# Sheet1.net
KiCad netlist of a schematic drawn in Altium Designer
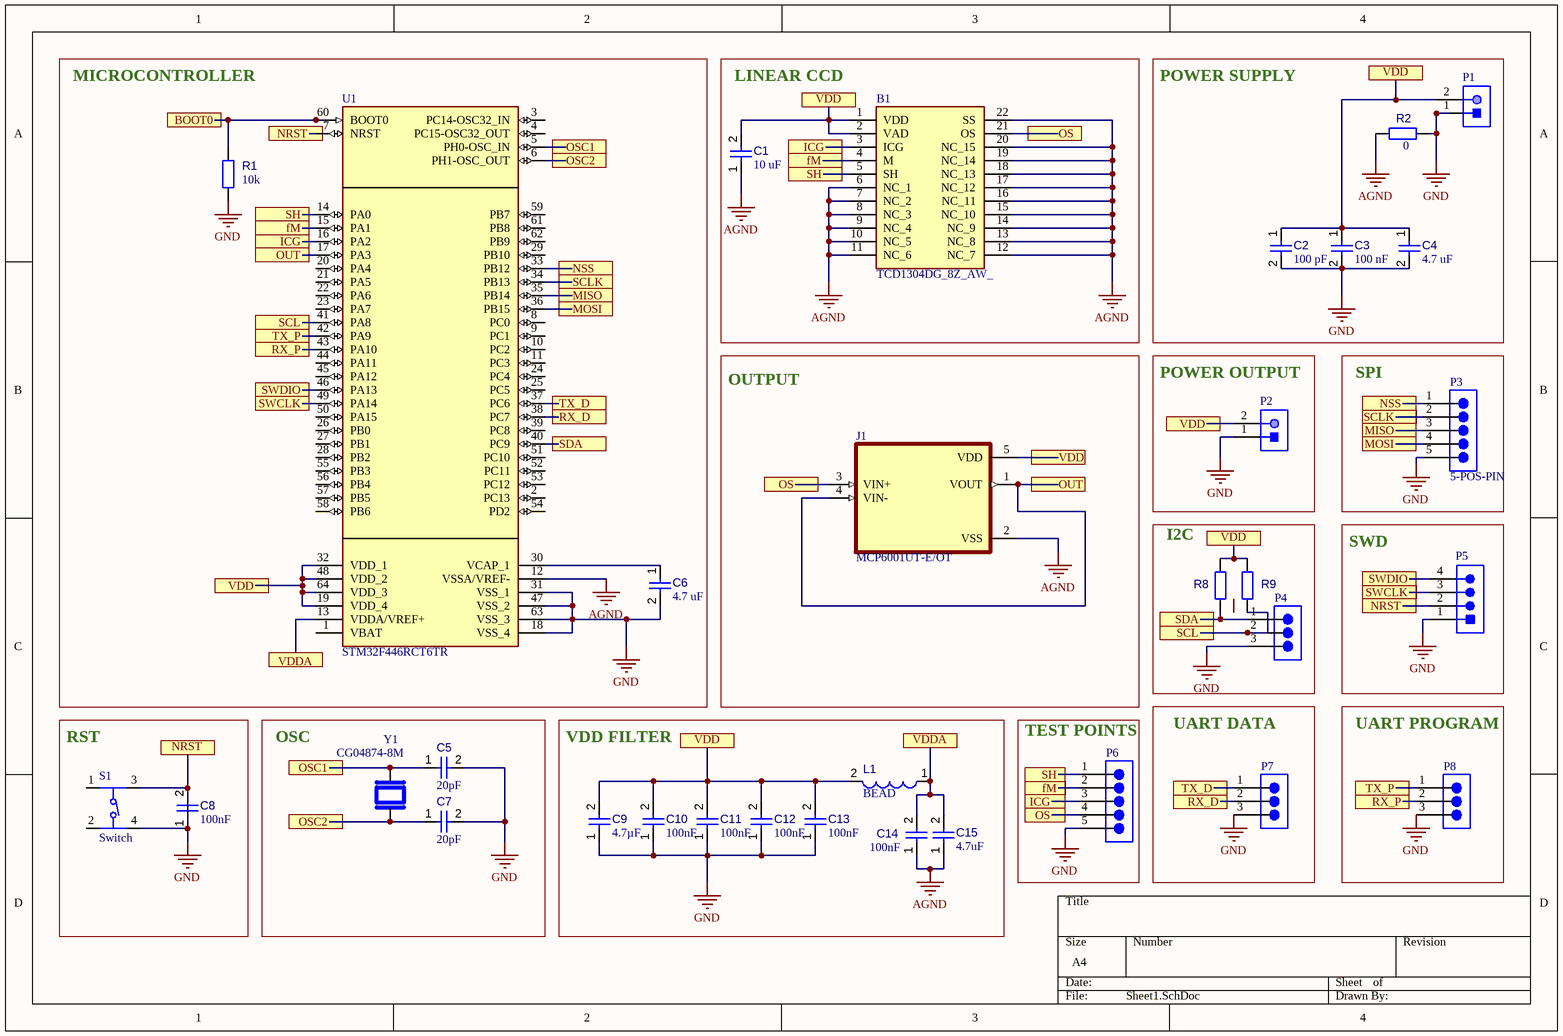
[diagram p0: Sheet1.SchDoc]

(export (version "E")
  (design (tool "Eeschema 10.0.6"))
  (components
    (comp (ref "B1")
      (value "TCD1304DG_8Z_AW_")
      (footprint "DIP1016W62P254L4160H372Q22N")
      (description "Image Sensors & Color Sensors CCD Linear Sensor 3648 8x20 54mm")
      (fields
        (field (name "MOUSER PART NUMBER") "757-TCD1304DG8ZAW")
        (field (name "MANUFACTURER_PART_NUMBER") "TCD1304DG(8Z,AW)")
      )
      (libsource (lib "Sensors") (part "TCD1304DG_8Z_AW_"))
    )
    (comp (ref "C1")
      (value "10 uF")
      (footprint "CAPC1005X56X25LL10T15")
      (description "Chip Capacitor, 0.1 uF, +/- 5%, 16 V, 0402 (1005 Metric)")
      (fields (field (name "TOLERANCE") "5%") (field (name "Comment") "Capacitor 0.1 uF +/- 5% 16 V 0402"))
      (libsource (lib "Francisco Spaltro") (part "CAP-NP-2"))
    )
    (comp (ref "C2")
      (value "100 pF")
      (footprint "CAPC2013X95X50LL10T25")
      (description "Chip Capacitor, 100 nF, +/- 10%, 50 V, 0805 (2012 Metric)")
      (fields (field (name "TOLERANCE") "10%") (field (name "Comment") "Capacitor 100 nF +/-10% 50 V 0805"))
      (libsource (lib "Francisco Spaltro") (part "CAP-NP-2"))
    )
    (comp (ref "C3")
      (value "100 nF")
      (footprint "CAPC2013X95X50LL10T25")
      (description "Chip Capacitor, 100 nF, +/- 10%, 50 V, 0805 (2012 Metric)")
      (fields (field (name "TOLERANCE") "10%") (field (name "Comment") "Capacitor 100 nF +/-10% 50 V 0805"))
      (libsource (lib "Francisco Spaltro") (part "CAP-NP-2"))
    )
    (comp (ref "C4")
      (value "4.7 uF")
      (footprint "CAPC2013X95X50LL10T25")
      (description "Chip Capacitor, 100 nF, +/- 10%, 50 V, 0805 (2012 Metric)")
      (fields (field (name "TOLERANCE") "10%") (field (name "Comment") "Capacitor 100 nF +/-10% 50 V 0805"))
      (libsource (lib "Francisco Spaltro") (part "CAP-NP-2"))
    )
    (comp (ref "C5")
      (value "20pF")
      (footprint "CAPC1005X56X25ML10T15")
      (description "Chip Capacitor, 0.5 pF, +/- 0.1pF, 25 V, 0402 (1005 Metric)")
      (fields
        (field (name "TOLERANCE") "20%")
        (field (name "Comment") "Capacitor 0.5 pF +/- 0.1pF 25 V 0402")
      )
      (libsource (lib "Francisco Spaltro") (part "CAP-NP-2"))
    )
    (comp (ref "C6")
      (value "4.7 uF")
      (footprint "CAPC2013X95X50LL10T25")
      (description "Chip Capacitor, 100 nF, +/- 10%, 50 V, 0805 (2012 Metric)")
      (fields (field (name "TOLERANCE") "10%") (field (name "Comment") "Capacitor 100 nF +/-10% 50 V 0805"))
      (libsource (lib "Francisco Spaltro") (part "CAP-NP-2"))
    )
    (comp (ref "C7")
      (value "20pF")
      (footprint "CAPC1005X56X25ML10T15")
      (description "Chip Capacitor, 0.5 pF, +/- 0.1pF, 25 V, 0402 (1005 Metric)")
      (fields
        (field (name "TOLERANCE") "20%")
        (field (name "Comment") "Capacitor 0.5 pF +/- 0.1pF 25 V 0402")
      )
      (libsource (lib "Francisco Spaltro") (part "CAP-NP-2"))
    )
    (comp (ref "C8")
      (value "100nF")
      (footprint "CAPC1005X56X25LL10T15")
      (description "Chip Capacitor, 0.1 uF, +/- 5%, 16 V, 0402 (1005 Metric)")
      (fields (field (name "TOLERANCE") "5%") (field (name "Comment") "Capacitor 0.1 uF +/- 5% 16 V 0402"))
      (libsource (lib "Francisco Spaltro") (part "CAP-NP-2"))
    )
    (comp (ref "C9")
      (value "4.7µF")
      (footprint "CAPC0603(1608)100_L")
      (description "Chip Capacitor, 4.7µF +/-20%, 10V, 0603, Thickness 1 mm")
      (fields (field (name "TOLERANCE") "10%") (field (name "Comment") "Capacitor 4.7µF +/-20% 10V 0603"))
      (libsource (lib "Francisco Spaltro") (part "CAP-NP-2"))
    )
    (comp (ref "C10")
      (value "100nF")
      (footprint "CAPC2013X95X50LL10T25")
      (description "Chip Capacitor, 100 nF, +/- 10%, 50 V, 0805 (2012 Metric)")
      (fields (field (name "TOLERANCE") "10%") (field (name "Comment") "Capacitor 100 nF +/-10% 50 V 0805"))
      (libsource (lib "Francisco Spaltro") (part "CAP-NP-2"))
    )
    (comp (ref "C11")
      (value "100nF")
      (footprint "CAPC2013X95X50LL10T25")
      (description "Chip Capacitor, 100 nF, +/- 10%, 50 V, 0805 (2012 Metric)")
      (fields (field (name "TOLERANCE") "10%") (field (name "Comment") "Capacitor 100 nF +/-10% 50 V 0805"))
      (libsource (lib "Francisco Spaltro") (part "CAP-NP-2"))
    )
    (comp (ref "C12")
      (value "100nF")
      (footprint "CAPC2013X95X50LL10T25")
      (description "Chip Capacitor, 100 nF, +/- 10%, 50 V, 0805 (2012 Metric)")
      (fields (field (name "TOLERANCE") "10%") (field (name "Comment") "Capacitor 100 nF +/-10% 50 V 0805"))
      (libsource (lib "Francisco Spaltro") (part "CAP-NP-2"))
    )
    (comp (ref "C13")
      (value "100nF")
      (footprint "CAPC2013X95X50LL10T25")
      (description "Chip Capacitor, 100 nF, +/- 10%, 50 V, 0805 (2012 Metric)")
      (fields (field (name "TOLERANCE") "10%") (field (name "Comment") "Capacitor 100 nF +/-10% 50 V 0805"))
      (libsource (lib "Francisco Spaltro") (part "CAP-NP-2"))
    )
    (comp (ref "C14")
      (value "100nF")
      (footprint "CAPC2013X95X50LL10T25")
      (description "Chip Capacitor, 100 nF, +/- 10%, 50 V, 0805 (2012 Metric)")
      (fields (field (name "TOLERANCE") "10%") (field (name "Comment") "Capacitor 100 nF +/-10% 50 V 0805"))
      (libsource (lib "Francisco Spaltro") (part "CAP-NP-2"))
    )
    (comp (ref "C15")
      (value "4.7uF")
      (footprint "CAPC2013X95X50LL10T25")
      (description "Chip Capacitor, 100 nF, +/- 10%, 50 V, 0805 (2012 Metric)")
      (fields (field (name "TOLERANCE") "10%") (field (name "Comment") "Capacitor 100 nF +/-10% 50 V 0805"))
      (libsource (lib "Francisco Spaltro") (part "CAP-NP-2"))
    )
    (comp (ref "J1")
      (value "MCP6001UT-E/OT")
      (footprint "SOT95P280X145-5N")
      (fields (field (name "MF") "Microchip"))
      (libsource (lib "Componentes") (part "MCP6001UT-E/OT"))
    )
    (comp (ref "L1")
      (value "BEAD")
      (footprint "WE-LQS 4018")
      (description "WE-LQS SMD Power Inductor, L=33 µH")
      (fields (field (name "TOLERANCE") "20%") (field (name "Comment") "74404042330"))
      (libsource (lib "Francisco Spaltro") (part "CMP-001-0020-1"))
    )
    (comp (ref "P1")
      (value "~")
      (footprint "JST-S2B-PH-K-S_V")
      (fields (field (name "MANUFACTURER") "Japan Solderless Terminals"))
      (libsource (lib "Francisco Spaltro") (part "CN-1P-M-R2"))
    )
    (comp (ref "P2")
      (value "~")
      (footprint "JST-S2B-PH-K-S_V")
      (fields (field (name "MANUFACTURER") "Japan Solderless Terminals"))
      (libsource (lib "Francisco Spaltro") (part "CN-1P-M-R2"))
    )
    (comp (ref "P3")
      (value "5-POS-PIN")
      (footprint "PCB_5POS_PIN")
      (libsource (lib "Componentes") (part "5-POS-PIN"))
    )
    (comp (ref "P4")
      (value "~")
      (footprint "PCB_3POS_PIN")
      (libsource (lib "Componentes") (part "3-POS-PIN"))
    )
    (comp (ref "P5")
      (value "~")
      (footprint "JST-S4B-XH-A(LF)(SN)_V")
      (fields (field (name "MANUFACTURER") "JST"))
      (libsource (lib "Francisco Spaltro") (part "CN-1P-M-R4"))
    )
    (comp (ref "P6")
      (value "~")
      (footprint "PCB_5POS_PIN")
      (libsource (lib "Componentes") (part "5-POS-PIN"))
    )
    (comp (ref "P7")
      (value "~")
      (footprint "PCB_3POS_PIN")
      (libsource (lib "Componentes") (part "3-POS-PIN"))
    )
    (comp (ref "P8")
      (value "~")
      (footprint "PCB_3POS_PIN")
      (libsource (lib "Componentes") (part "3-POS-PIN"))
    )
    (comp (ref "R1")
      (value "10k")
      (footprint "RESC0402(1005)_L")
      (description "10K 0.063W 1% 0402 (1005 Metric)  SMD")
      (fields (field (name "POWER") "63mW") (field (name "TOLERANCE") "1%"))
      (libsource (lib "") (part "10KR2F_2"))
    )
    (comp (ref "R2")
      (value "0")
      (footprint "RESC0402(1005)_L")
      (description "10K 0.063W 1% 0402 (1005 Metric)  SMD")
      (fields (field (name "POWER") "63mW") (field (name "TOLERANCE") "1%"))
      (libsource (lib "Francisco Spaltro") (part "10KR2F"))
    )
    (comp (ref "R8")
      (value "10KR2F")
      (footprint "RESC0402(1005)_L")
      (description "10K 0.063W 1% 0402 (1005 Metric)  SMD")
      (fields (field (name "POWER") "63mW") (field (name "TOLERANCE") "1%"))
      (libsource (lib "") (part "10KR2F_1"))
    )
    (comp (ref "R9")
      (value "10KR2F")
      (footprint "RESC0402(1005)_L")
      (description "10K 0.063W 1% 0402 (1005 Metric)  SMD")
      (fields (field (name "POWER") "63mW") (field (name "TOLERANCE") "1%"))
      (libsource (lib "") (part "10KR2F_1"))
    )
    (comp (ref "S1")
      (value "Switch")
      (footprint "430152070826 Switch")
      (description "Tactile Switch SPST-NO Top Actuated Surface Mount")
      (fields (field (name "MF") "WÃ¼rth Elektronik") (field (name "MP") "430152070826"))
      (libsource (lib "Componentes") (part "Switch"))
    )
    (comp (ref "U1")
      (value "STM32F446RCT6TR")
      (footprint "QFP50P1200X1200X160-64N")
      (fields (field (name "MF") "STMicroelectronics"))
      (libsource (lib "IC") (part "STM32F446RCT6TR"))
    )
    (comp (ref "Y1")
      (value "CG04874-8M")
      (footprint "XTALDFN320X250X100-2N")
      (description "8 MHz ±20ppm Crystal 8pF 500 Ohms 2-SMD, No Lead")
      (fields (field (name "MF") "NDK America, Inc."))
      (libsource (lib "Componentes") (part "CG04874-8M"))
    )
  )
  (nets
    (net (code "1") (name "/BOOT0") (class "Default")
      (node (ref "R1") (pin "2") (pinfunction "2_2") (pintype "passive"))
      (node (ref "U1") (pin "60") (pinfunction "BOOT0_60") (pintype "input"))
    )
    (net (code "2") (name "/ICG") (class "Default")
      (node (ref "B1") (pin "3") (pinfunction "ICG_3") (pintype "passive"))
      (node (ref "P6") (pin "3") (pinfunction "3_3") (pintype "passive"))
      (node (ref "U1") (pin "16") (pinfunction "PA2_16") (pintype "bidirectional"))
    )
    (net (code "3") (name "/MISO") (class "Default")
      (node (ref "P3") (pin "3") (pinfunction "3_3") (pintype "passive"))
      (node (ref "U1") (pin "35") (pinfunction "PB14_35") (pintype "bidirectional"))
    )
    (net (code "4") (name "/MOSI") (class "Default")
      (node (ref "P3") (pin "4") (pinfunction "4_4") (pintype "passive"))
      (node (ref "U1") (pin "36") (pinfunction "PB15_36") (pintype "bidirectional"))
    )
    (net (code "5") (name "/NRST") (class "Default")
      (node (ref "C8") (pin "2") (pinfunction "2_2") (pintype "passive"))
      (node (ref "P5") (pin "2") (pinfunction "2_2") (pintype "passive"))
      (node (ref "S1") (pin "3") (pinfunction "3_3") (pintype "passive"))
      (node (ref "U1") (pin "7") (pinfunction "NRST_7") (pintype "bidirectional"))
    )
    (net (code "6") (name "/NSS") (class "Default")
      (node (ref "P3") (pin "1") (pinfunction "1_1") (pintype "passive"))
      (node (ref "U1") (pin "33") (pinfunction "PB12_33") (pintype "bidirectional"))
    )
    (net (code "7") (name "/OS") (class "Default")
      (node (ref "B1") (pin "21") (pinfunction "OS_21") (pintype "passive"))
      (node (ref "J1") (pin "3") (pinfunction "VIN+_3") (pintype "input"))
      (node (ref "P6") (pin "4") (pinfunction "4_4") (pintype "passive"))
    )
    (net (code "8") (name "/OSC1") (class "Default")
      (node (ref "C5") (pin "1") (pinfunction "1_1") (pintype "passive"))
      (node (ref "U1") (pin "5") (pinfunction "PH0-OSC_IN_5") (pintype "bidirectional"))
      (node (ref "Y1") (pin "2") (pinfunction "2_2") (pintype "passive"))
    )
    (net (code "9") (name "/OSC2") (class "Default")
      (node (ref "C7") (pin "1") (pinfunction "1_1") (pintype "passive"))
      (node (ref "U1") (pin "6") (pinfunction "PH1-OSC_OUT_6") (pintype "bidirectional"))
      (node (ref "Y1") (pin "1") (pinfunction "1_1") (pintype "passive"))
    )
    (net (code "10") (name "/OUT") (class "Default")
      (node (ref "J1") (pin "1") (pinfunction "VOUT_1") (pintype "output"))
      (node (ref "J1") (pin "4") (pinfunction "VIN-_4") (pintype "input"))
      (node (ref "U1") (pin "17") (pinfunction "PA3_17") (pintype "bidirectional"))
    )
    (net (code "11") (name "/RX_D") (class "Default")
      (node (ref "P7") (pin "2") (pinfunction "2_2") (pintype "passive"))
      (node (ref "U1") (pin "38") (pinfunction "PC7_38") (pintype "bidirectional"))
    )
    (net (code "12") (name "/RX_P") (class "Default")
      (node (ref "P8") (pin "2") (pinfunction "2_2") (pintype "passive"))
      (node (ref "U1") (pin "43") (pinfunction "PA10_43") (pintype "bidirectional"))
    )
    (net (code "13") (name "/SCL") (class "Default")
      (node (ref "P4") (pin "2") (pinfunction "2_2") (pintype "passive"))
      (node (ref "R9") (pin "2") (pinfunction "2_2") (pintype "passive"))
      (node (ref "U1") (pin "41") (pinfunction "PA8_41") (pintype "bidirectional"))
    )
    (net (code "14") (name "/SCLK") (class "Default")
      (node (ref "P3") (pin "2") (pinfunction "2_2") (pintype "passive"))
      (node (ref "U1") (pin "34") (pinfunction "PB13_34") (pintype "bidirectional"))
    )
    (net (code "15") (name "/SDA") (class "Default")
      (node (ref "P4") (pin "1") (pinfunction "1_1") (pintype "passive"))
      (node (ref "R8") (pin "2") (pinfunction "2_2") (pintype "passive"))
      (node (ref "U1") (pin "40") (pinfunction "PC9_40") (pintype "bidirectional"))
    )
    (net (code "16") (name "/SH") (class "Default")
      (node (ref "B1") (pin "5") (pinfunction "SH_5") (pintype "passive"))
      (node (ref "P6") (pin "1") (pinfunction "1_1") (pintype "passive"))
      (node (ref "U1") (pin "14") (pinfunction "PA0_14") (pintype "bidirectional"))
    )
    (net (code "17") (name "/SWCLK") (class "Default")
      (node (ref "P5") (pin "3") (pinfunction "3_3") (pintype "passive"))
      (node (ref "U1") (pin "49") (pinfunction "PA14_49") (pintype "bidirectional"))
    )
    (net (code "18") (name "/SWDIO") (class "Default")
      (node (ref "P5") (pin "4") (pinfunction "4_4") (pintype "passive"))
      (node (ref "U1") (pin "46") (pinfunction "PA13_46") (pintype "bidirectional"))
    )
    (net (code "19") (name "/TX_D") (class "Default")
      (node (ref "P7") (pin "1") (pinfunction "1_1") (pintype "passive"))
      (node (ref "U1") (pin "37") (pinfunction "PC6_37") (pintype "bidirectional"))
    )
    (net (code "20") (name "/TX_P") (class "Default")
      (node (ref "P8") (pin "1") (pinfunction "1_1") (pintype "passive"))
      (node (ref "U1") (pin "42") (pinfunction "PA9_42") (pintype "bidirectional"))
    )
    (net (code "21") (name "/VDD") (class "Default")
      (node (ref "B1") (pin "1") (pinfunction "VDD_1") (pintype "power_in"))
      (node (ref "B1") (pin "2") (pinfunction "VAD_2") (pintype "power_in"))
      (node (ref "C1") (pin "2") (pinfunction "2_2") (pintype "passive"))
      (node (ref "C10") (pin "2") (pinfunction "2_2") (pintype "passive"))
      (node (ref "C11") (pin "2") (pinfunction "2_2") (pintype "passive"))
      (node (ref "C12") (pin "2") (pinfunction "2_2") (pintype "passive"))
      (node (ref "C13") (pin "2") (pinfunction "2_2") (pintype "passive"))
      (node (ref "C2") (pin "1") (pinfunction "1_1") (pintype "passive"))
      (node (ref "C3") (pin "1") (pinfunction "1_1") (pintype "passive"))
      (node (ref "C4") (pin "1") (pinfunction "1_1") (pintype "passive"))
      (node (ref "C9") (pin "2") (pinfunction "2_2") (pintype "passive"))
      (node (ref "J1") (pin "5") (pinfunction "VDD_5") (pintype "power_in"))
      (node (ref "L1") (pin "2") (pinfunction "2_2") (pintype "passive"))
      (node (ref "P1") (pin "2") (pinfunction "2_2") (pintype "passive"))
      (node (ref "P2") (pin "2") (pinfunction "2_2") (pintype "passive"))
      (node (ref "R8") (pin "1") (pinfunction "1_1") (pintype "passive"))
      (node (ref "R9") (pin "1") (pinfunction "1_1") (pintype "passive"))
      (node (ref "U1") (pin "19") (pinfunction "VDD_4_19") (pintype "power_in"))
      (node (ref "U1") (pin "32") (pinfunction "VDD_1_32") (pintype "power_in"))
      (node (ref "U1") (pin "48") (pinfunction "VDD_2_48") (pintype "power_in"))
      (node (ref "U1") (pin "64") (pinfunction "VDD_3_64") (pintype "power_in"))
    )
    (net (code "22") (name "/VDDA") (class "Default")
      (node (ref "C14") (pin "2") (pinfunction "2_2") (pintype "passive"))
      (node (ref "C15") (pin "2") (pinfunction "2_2") (pintype "passive"))
      (node (ref "L1") (pin "1") (pinfunction "1_1") (pintype "passive"))
      (node (ref "U1") (pin "13") (pinfunction "VDDA/VREF+_13") (pintype "power_in"))
    )
    (net (code "23") (name "/fM") (class "Default")
      (node (ref "B1") (pin "4") (pinfunction "M_4") (pintype "passive"))
      (node (ref "P6") (pin "2") (pinfunction "2_2") (pintype "passive"))
      (node (ref "U1") (pin "15") (pinfunction "PA1_15") (pintype "bidirectional"))
    )
    (net (code "24") (name "AGND") (class "Default")
      (node (ref "B1") (pin "10") (pinfunction "NC_5_10") (pintype "passive"))
      (node (ref "B1") (pin "11") (pinfunction "NC_6_11") (pintype "passive"))
      (node (ref "B1") (pin "12") (pinfunction "NC_7_12") (pintype "passive"))
      (node (ref "B1") (pin "13") (pinfunction "NC_8_13") (pintype "passive"))
      (node (ref "B1") (pin "14") (pinfunction "NC_9_14") (pintype "passive"))
      (node (ref "B1") (pin "15") (pinfunction "NC_10_15") (pintype "passive"))
      (node (ref "B1") (pin "16") (pinfunction "NC_11_16") (pintype "passive"))
      (node (ref "B1") (pin "17") (pinfunction "NC_12_17") (pintype "passive"))
      (node (ref "B1") (pin "18") (pinfunction "NC_13_18") (pintype "passive"))
      (node (ref "B1") (pin "19") (pinfunction "NC_14_19") (pintype "passive"))
      (node (ref "B1") (pin "20") (pinfunction "NC_15_20") (pintype "passive"))
      (node (ref "B1") (pin "22") (pinfunction "SS_22") (pintype "passive"))
      (node (ref "B1") (pin "6") (pinfunction "NC_1_6") (pintype "passive"))
      (node (ref "B1") (pin "7") (pinfunction "NC_2_7") (pintype "passive"))
      (node (ref "B1") (pin "8") (pinfunction "NC_3_8") (pintype "passive"))
      (node (ref "B1") (pin "9") (pinfunction "NC_4_9") (pintype "passive"))
      (node (ref "C1") (pin "1") (pinfunction "1_1") (pintype "passive"))
      (node (ref "C14") (pin "1") (pinfunction "1_1") (pintype "passive"))
      (node (ref "C15") (pin "1") (pinfunction "1_1") (pintype "passive"))
      (node (ref "J1") (pin "2") (pinfunction "VSS_2") (pintype "power_in"))
      (node (ref "R2") (pin "2") (pinfunction "2_2") (pintype "passive"))
      (node (ref "U1") (pin "12") (pinfunction "VSSA/VREF-_12") (pintype "power_in"))
    )
    (net (code "25") (name "GND") (class "Default")
      (node (ref "C10") (pin "1") (pinfunction "1_1") (pintype "passive"))
      (node (ref "C11") (pin "1") (pinfunction "1_1") (pintype "passive"))
      (node (ref "C12") (pin "1") (pinfunction "1_1") (pintype "passive"))
      (node (ref "C13") (pin "1") (pinfunction "1_1") (pintype "passive"))
      (node (ref "C2") (pin "2") (pinfunction "2_2") (pintype "passive"))
      (node (ref "C3") (pin "2") (pinfunction "2_2") (pintype "passive"))
      (node (ref "C4") (pin "2") (pinfunction "2_2") (pintype "passive"))
      (node (ref "C5") (pin "2") (pinfunction "2_2") (pintype "passive"))
      (node (ref "C6") (pin "2") (pinfunction "2_2") (pintype "passive"))
      (node (ref "C7") (pin "2") (pinfunction "2_2") (pintype "passive"))
      (node (ref "C8") (pin "1") (pinfunction "1_1") (pintype "passive"))
      (node (ref "C9") (pin "1") (pinfunction "1_1") (pintype "passive"))
      (node (ref "P1") (pin "1") (pinfunction "1_1") (pintype "passive"))
      (node (ref "P2") (pin "1") (pinfunction "1_1") (pintype "passive"))
      (node (ref "P3") (pin "5") (pinfunction "5_5") (pintype "passive"))
      (node (ref "P4") (pin "3") (pinfunction "3_3") (pintype "passive"))
      (node (ref "P5") (pin "1") (pinfunction "1_1") (pintype "passive"))
      (node (ref "P6") (pin "5") (pinfunction "5_5") (pintype "passive"))
      (node (ref "P7") (pin "3") (pinfunction "3_3") (pintype "passive"))
      (node (ref "P8") (pin "3") (pinfunction "3_3") (pintype "passive"))
      (node (ref "R1") (pin "1") (pinfunction "1_1") (pintype "passive"))
      (node (ref "R2") (pin "1") (pinfunction "1_1") (pintype "passive"))
      (node (ref "S1") (pin "4") (pinfunction "4_4") (pintype "passive"))
      (node (ref "U1") (pin "18") (pinfunction "VSS_4_18") (pintype "power_in"))
      (node (ref "U1") (pin "31") (pinfunction "VSS_1_31") (pintype "power_in"))
      (node (ref "U1") (pin "47") (pinfunction "VSS_2_47") (pintype "power_in"))
      (node (ref "U1") (pin "63") (pinfunction "VSS_3_63") (pintype "power_in"))
    )
    (net (code "26") (name "Net-(U1-VCAP_1)") (class "Default")
      (node (ref "C6") (pin "1") (pinfunction "1_1") (pintype "passive"))
      (node (ref "U1") (pin "30") (pinfunction "VCAP_1_30") (pintype "power_in"))
    )
    (net (code "27") (name "unconnected-(S1-Pad1)") (class "Default")
      (node (ref "S1") (pin "1") (pinfunction "1_1") (pintype "passive"))
    )
    (net (code "28") (name "unconnected-(S1-Pad2)") (class "Default")
      (node (ref "S1") (pin "2") (pinfunction "2_2") (pintype "passive"))
    )
    (net (code "29") (name "unconnected-(U1-PA4-Pad20)") (class "Default")
      (node (ref "U1") (pin "20") (pinfunction "PA4_20") (pintype "bidirectional"))
    )
    (net (code "30") (name "unconnected-(U1-PA5-Pad21)") (class "Default")
      (node (ref "U1") (pin "21") (pinfunction "PA5_21") (pintype "bidirectional"))
    )
    (net (code "31") (name "unconnected-(U1-PA6-Pad22)") (class "Default")
      (node (ref "U1") (pin "22") (pinfunction "PA6_22") (pintype "bidirectional"))
    )
    (net (code "32") (name "unconnected-(U1-PA7-Pad23)") (class "Default")
      (node (ref "U1") (pin "23") (pinfunction "PA7_23") (pintype "bidirectional"))
    )
    (net (code "33") (name "unconnected-(U1-PA11-Pad44)") (class "Default")
      (node (ref "U1") (pin "44") (pinfunction "PA11_44") (pintype "bidirectional"))
    )
    (net (code "34") (name "unconnected-(U1-PA12-Pad45)") (class "Default")
      (node (ref "U1") (pin "45") (pinfunction "PA12_45") (pintype "bidirectional"))
    )
    (net (code "35") (name "unconnected-(U1-PA15-Pad50)") (class "Default")
      (node (ref "U1") (pin "50") (pinfunction "PA15_50") (pintype "bidirectional"))
    )
    (net (code "36") (name "unconnected-(U1-PB0-Pad26)") (class "Default")
      (node (ref "U1") (pin "26") (pinfunction "PB0_26") (pintype "bidirectional"))
    )
    (net (code "37") (name "unconnected-(U1-PB1-Pad27)") (class "Default")
      (node (ref "U1") (pin "27") (pinfunction "PB1_27") (pintype "bidirectional"))
    )
    (net (code "38") (name "unconnected-(U1-PB2-Pad28)") (class "Default")
      (node (ref "U1") (pin "28") (pinfunction "PB2_28") (pintype "bidirectional"))
    )
    (net (code "39") (name "unconnected-(U1-PB3-Pad55)") (class "Default")
      (node (ref "U1") (pin "55") (pinfunction "PB3_55") (pintype "bidirectional"))
    )
    (net (code "40") (name "unconnected-(U1-PB4-Pad56)") (class "Default")
      (node (ref "U1") (pin "56") (pinfunction "PB4_56") (pintype "bidirectional"))
    )
    (net (code "41") (name "unconnected-(U1-PB5-Pad57)") (class "Default")
      (node (ref "U1") (pin "57") (pinfunction "PB5_57") (pintype "bidirectional"))
    )
    (net (code "42") (name "unconnected-(U1-PB6-Pad58)") (class "Default")
      (node (ref "U1") (pin "58") (pinfunction "PB6_58") (pintype "bidirectional"))
    )
    (net (code "43") (name "unconnected-(U1-PB7-Pad59)") (class "Default")
      (node (ref "U1") (pin "59") (pinfunction "PB7_59") (pintype "bidirectional"))
    )
    (net (code "44") (name "unconnected-(U1-PB8-Pad61)") (class "Default")
      (node (ref "U1") (pin "61") (pinfunction "PB8_61") (pintype "bidirectional"))
    )
    (net (code "45") (name "unconnected-(U1-PB9-Pad62)") (class "Default")
      (node (ref "U1") (pin "62") (pinfunction "PB9_62") (pintype "bidirectional"))
    )
    (net (code "46") (name "unconnected-(U1-PB10-Pad29)") (class "Default")
      (node (ref "U1") (pin "29") (pinfunction "PB10_29") (pintype "bidirectional"))
    )
    (net (code "47") (name "unconnected-(U1-PC0-Pad8)") (class "Default")
      (node (ref "U1") (pin "8") (pinfunction "PC0_8") (pintype "bidirectional"))
    )
    (net (code "48") (name "unconnected-(U1-PC1-Pad9)") (class "Default")
      (node (ref "U1") (pin "9") (pinfunction "PC1_9") (pintype "bidirectional"))
    )
    (net (code "49") (name "unconnected-(U1-PC2-Pad10)") (class "Default")
      (node (ref "U1") (pin "10") (pinfunction "PC2_10") (pintype "bidirectional"))
    )
    (net (code "50") (name "unconnected-(U1-PC3-Pad11)") (class "Default")
      (node (ref "U1") (pin "11") (pinfunction "PC3_11") (pintype "bidirectional"))
    )
    (net (code "51") (name "unconnected-(U1-PC4-Pad24)") (class "Default")
      (node (ref "U1") (pin "24") (pinfunction "PC4_24") (pintype "bidirectional"))
    )
    (net (code "52") (name "unconnected-(U1-PC5-Pad25)") (class "Default")
      (node (ref "U1") (pin "25") (pinfunction "PC5_25") (pintype "bidirectional"))
    )
    (net (code "53") (name "unconnected-(U1-PC8-Pad39)") (class "Default")
      (node (ref "U1") (pin "39") (pinfunction "PC8_39") (pintype "bidirectional"))
    )
    (net (code "54") (name "unconnected-(U1-PC10-Pad51)") (class "Default")
      (node (ref "U1") (pin "51") (pinfunction "PC10_51") (pintype "bidirectional"))
    )
    (net (code "55") (name "unconnected-(U1-PC11-Pad52)") (class "Default")
      (node (ref "U1") (pin "52") (pinfunction "PC11_52") (pintype "bidirectional"))
    )
    (net (code "56") (name "unconnected-(U1-PC12-Pad53)") (class "Default")
      (node (ref "U1") (pin "53") (pinfunction "PC12_53") (pintype "bidirectional"))
    )
    (net (code "57") (name "unconnected-(U1-PC13-Pad2)") (class "Default")
      (node (ref "U1") (pin "2") (pinfunction "PC13_2") (pintype "bidirectional"))
    )
    (net (code "58") (name "unconnected-(U1-PC14-OSC32_IN-Pad3)") (class "Default")
      (node (ref "U1") (pin "3") (pinfunction "PC14-OSC32_IN_3") (pintype "bidirectional"))
    )
    (net (code "59") (name "unconnected-(U1-PC15-OSC32_OUT-Pad4)") (class "Default")
      (node (ref "U1") (pin "4") (pinfunction "PC15-OSC32_OUT_4") (pintype "bidirectional"))
    )
    (net (code "60") (name "unconnected-(U1-PD2-Pad54)") (class "Default")
      (node (ref "U1") (pin "54") (pinfunction "PD2_54") (pintype "bidirectional"))
    )
    (net (code "61") (name "unconnected-(U1-VBAT-Pad1)") (class "Default")
      (node (ref "U1") (pin "1") (pinfunction "VBAT_1") (pintype "power_in"))
    )
  )
)
